# Optoacoplador.net
KiCad netlist of a schematic drawn in Altium Designer
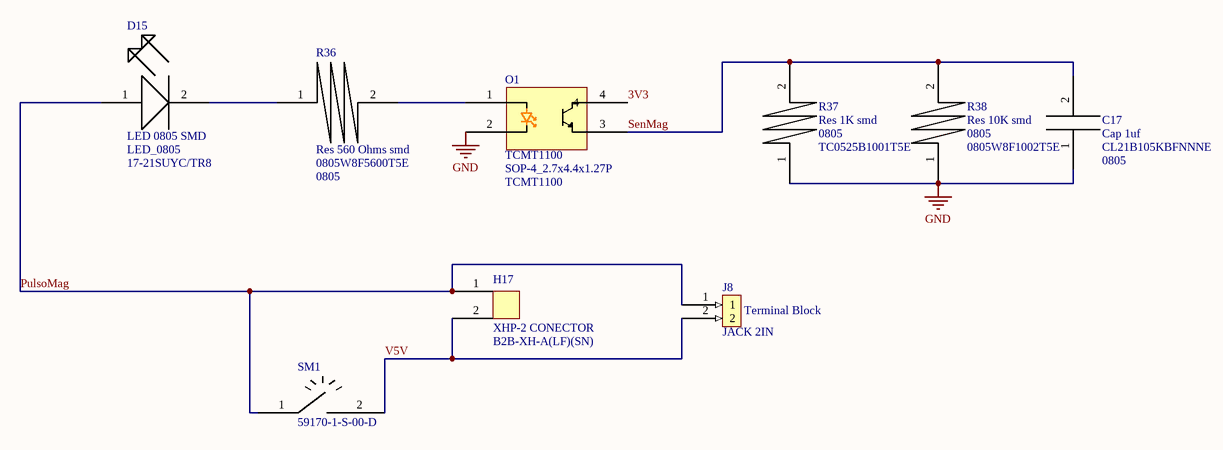
[diagram p0: Optoacoplador.SchDoc]

(export (version "E")
  (design (tool "Eeschema 10.0.6"))
  (components
    (comp (ref "C17")
      (value "Cap 1uf")
      (footprint "CAP 1UFSMD")
      (fields (field (name "MFR.PART #") "CL21B105KBFNNNE") (field (name "PACKAGE") "0805"))
      (libsource (lib "Integrated_Library") (part "Cap 1uf"))
    )
    (comp (ref "D15")
      (value "LED 0805 SMD")
      (footprint "LED SMD Amarillo")
      (description "LED 0805 Yellow")
      (fields (field (name "PACKAGE") "LED_0805") (field (name "MFR.PART #") "17-21SUYC/TR8"))
      (libsource (lib "Integrated_Library") (part "LED 0805 SMD"))
    )
    (comp (ref "H17")
      (value "XHP-2 CONECTOR")
      (footprint "CONECTOR 2 PINES")
      (description "CONECTOR JST-XH 2 PINES")
      (fields (field (name "SUPPLIER NUMBER PART") "B2B-XH-A(LF)(SN)"))
      (libsource (lib "Practica 1") (part "B2B-XH-A(LF)(SN)"))
    )
    (comp (ref "J8")
      (value "JACK 2IN")
      (footprint "Terminal Blocks 2in")
      (description "Pluggable Terminal Blocks WR-TBL Mod312 5.08mm 2Pin Opn Hztl PCBHdr")
      (fields
        (field (name "MANUFACTURER") "Wurth Electronics")
        (field (name "MANUFACTURER PART NUMBER") "691312510002")
      )
      (libsource (lib "seguintII") (part "JACK 2IN"))
    )
    (comp (ref "O1")
      (value "TCMT1100")
      (footprint "TCMT110")
      (fields (field (name "PACKAGE") "SOP-4_2.7x4.4x1.27P") (field (name "MFR.PART #") "TCMT1100"))
      (libsource (lib "Integrated_Library") (part "TCMT110"))
    )
    (comp (ref "R36")
      (value "Res 560 Ohms smd")
      (footprint "RES 560")
      (description "Res 560 ohms smd")
      (fields (field (name "MFR.PART #") "0805W8F5600T5E") (field (name "PACKAGE") "0805"))
      (libsource (lib "Integrated_Library") (part "Res 560 Ohms smd"))
    )
    (comp (ref "R37")
      (value "Res 1K smd")
      (footprint "RES 1K")
      (fields (field (name "PACKAGE") "0805") (field (name "MFR.PART #") "TC0525B1001T5E"))
      (libsource (lib "Integrated_Library") (part "Res 1K smd"))
    )
    (comp (ref "R38")
      (value "Res 10K smd")
      (footprint "RES 10K")
      (description "10K")
      (fields (field (name "PACKAGE") "0805") (field (name "MFR.PART #") "0805W8F1002T5E"))
      (libsource (lib "Integrated_Library") (part "Res 10K smd"))
    )
    (comp (ref "SM1")
      (value "59170-1-S-00-D")
      (footprint "Switch Magnetico")
      (libsource (lib "Integrated_Library") (part "59170-1-S-00-D"))
    )
  )
  (nets
    (net (code "1") (name "/3V3") (class "Default")
      (node (ref "O1") (pin "4") (pinfunction "4_4") (pintype "passive"))
    )
    (net (code "2") (name "/PulsoMag") (class "Default")
      (node (ref "D15") (pin "1") (pinfunction "1_1") (pintype "passive"))
      (node (ref "H17") (pin "1") (pinfunction "1_1") (pintype "passive"))
      (node (ref "J8") (pin "1") (pinfunction "1_1") (pintype "input"))
      (node (ref "SM1") (pin "1") (pinfunction "1_1") (pintype "passive"))
    )
    (net (code "3") (name "/SenMag") (class "Default")
      (node (ref "C17") (pin "2") (pinfunction "2_2") (pintype "passive"))
      (node (ref "O1") (pin "3") (pinfunction "3_3") (pintype "passive"))
      (node (ref "R37") (pin "2") (pinfunction "2_2") (pintype "passive"))
      (node (ref "R38") (pin "2") (pinfunction "2_2") (pintype "passive"))
    )
    (net (code "4") (name "/V5V") (class "Default")
      (node (ref "H17") (pin "2") (pinfunction "2_2") (pintype "passive"))
      (node (ref "J8") (pin "2") (pinfunction "2_2") (pintype "input"))
      (node (ref "SM1") (pin "2") (pinfunction "2_2") (pintype "passive"))
    )
    (net (code "5") (name "GND") (class "Default")
      (node (ref "C17") (pin "1") (pinfunction "1_1") (pintype "passive"))
      (node (ref "O1") (pin "2") (pinfunction "2_2") (pintype "passive"))
      (node (ref "R37") (pin "1") (pinfunction "1_1") (pintype "passive"))
      (node (ref "R38") (pin "1") (pinfunction "1_1") (pintype "passive"))
    )
    (net (code "6") (name "Net-(D15-Pad2)") (class "Default")
      (node (ref "D15") (pin "2") (pinfunction "2_2") (pintype "passive"))
      (node (ref "R36") (pin "1") (pinfunction "1_1") (pintype "passive"))
    )
    (net (code "7") (name "Net-(O1-Pad1)") (class "Default")
      (node (ref "O1") (pin "1") (pinfunction "1_1") (pintype "passive"))
      (node (ref "R36") (pin "2") (pinfunction "2_2") (pintype "passive"))
    )
  )
)
